# interfaces.net
KiCad netlist of a schematic drawn in Altium Designer
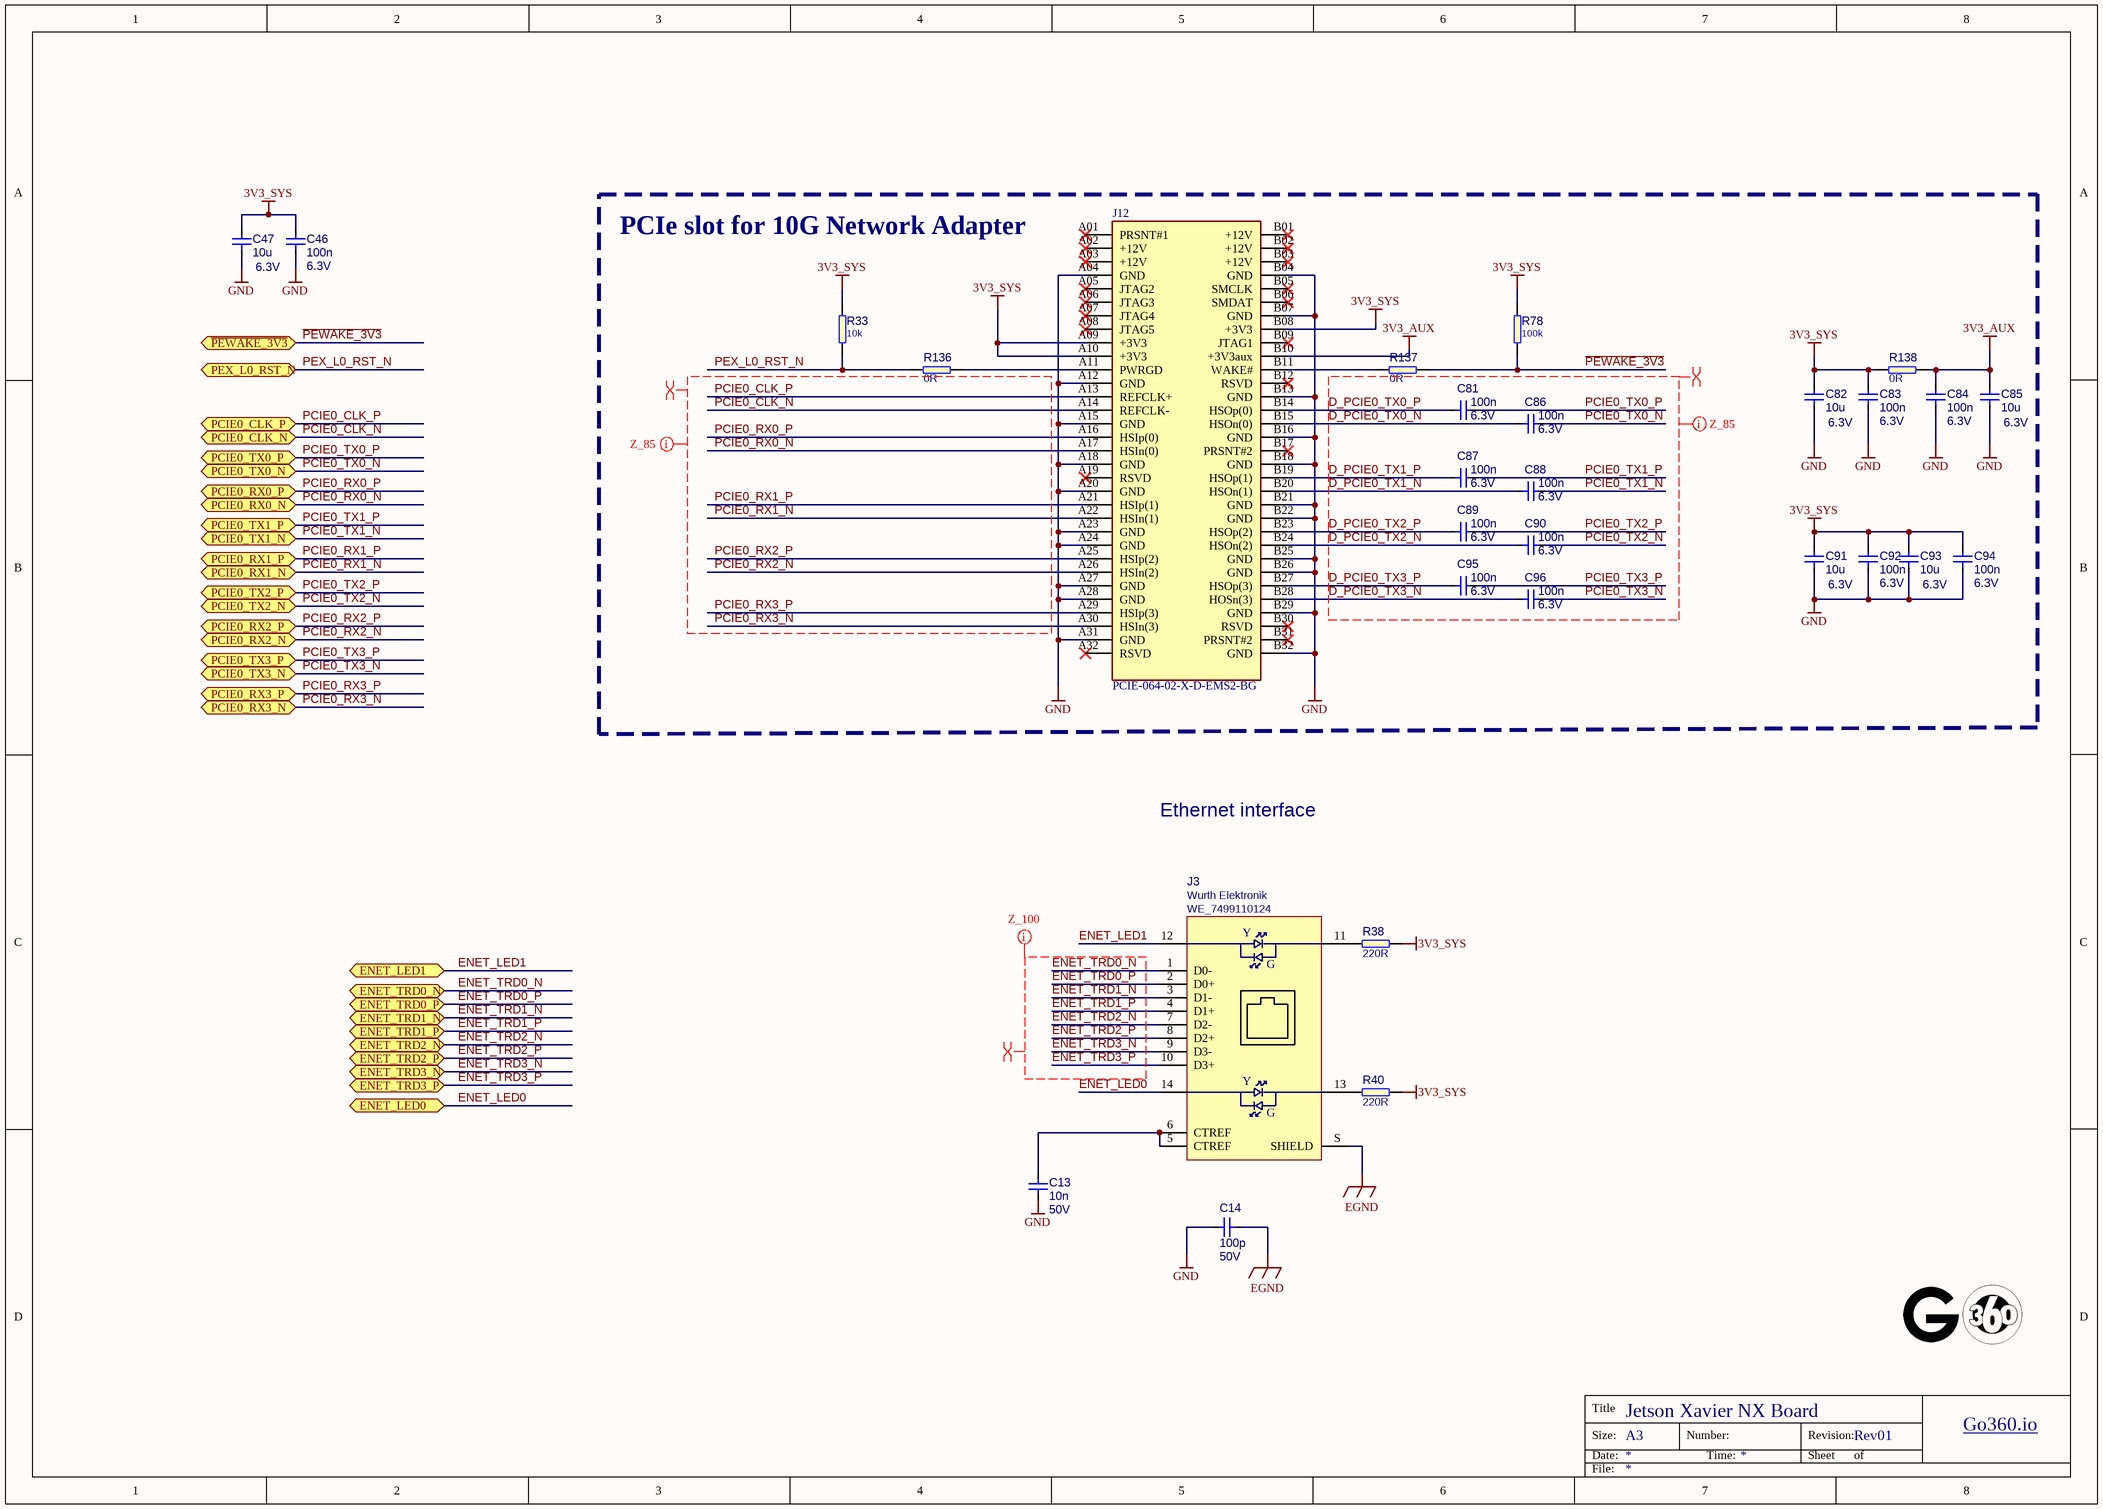
[diagram p0: interfaces.SchDoc]

(export (version "E")
  (design (tool "Eeschema 10.0.6"))
  (components
    (comp (ref "C13")
      (value "10n")
      (footprint "0402")
      (description "MLCC SMT Capacitor 10 nF 0402")
      (fields
        (field (name "PARTNUMBER") "C_10n_0402")
        (field (name "MANUFACTURER") "AVX")
        (field (name "VOLTAGE") "50V")
      )
      (libsource (lib "jetson-nano-baseboard") (part "C_10n_0402"))
    )
    (comp (ref "C14")
      (value "100p")
      (footprint "0805")
      (description "MLCC SMT Capacitor 100pF 0805")
      (fields
        (field (name "PARTNUMBER") "C_100p_0805")
        (field (name "MANUFACTURER") "AVX")
        (field (name "VOLTAGE") "50V")
      )
      (libsource (lib "jetson-nano-baseboard") (part "C_100p_0805"))
    )
    (comp (ref "C46")
      (value "100n")
      (footprint "0402")
      (description "MLCC SMT Capacitor 100n 0402")
      (fields
        (field (name "MANUFACTURER") "TDK")
        (field (name "PARTNUMBER") "C_100n_0402")
        (field (name "VOLTAGE") "6.3V")
      )
      (libsource (lib "jetson-nano-baseboard") (part "C_100n_0402"))
    )
    (comp (ref "C47")
      (value "10u")
      (footprint "0603")
      (description "MLCC SMT Capacitor 10uF 0603")
      (fields
        (field (name "MANUFACTURER") "Walsin")
        (field (name "PARTNUMBER") "C_10u_0603")
        (field (name "VOLTAGE") "6.3V")
      )
      (libsource (lib "jetson-nano-baseboard") (part "C_10u_0603"))
    )
    (comp (ref "C81")
      (value "100n")
      (footprint "0402")
      (description "MLCC SMT Capacitor 100n 0402")
      (fields
        (field (name "MANUFACTURER") "TDK")
        (field (name "PARTNUMBER") "C_100n_0402")
        (field (name "VOLTAGE") "6.3V")
      )
      (libsource (lib "jetson-nano-baseboard") (part "C_100n_0402"))
    )
    (comp (ref "C82")
      (value "10u")
      (footprint "0603")
      (description "MLCC SMT Capacitor 10uF 0603")
      (fields
        (field (name "MANUFACTURER") "Walsin")
        (field (name "PARTNUMBER") "C_10u_0603")
        (field (name "VOLTAGE") "6.3V")
      )
      (libsource (lib "jetson-nano-baseboard") (part "C_10u_0603"))
    )
    (comp (ref "C83")
      (value "100n")
      (footprint "0402")
      (description "MLCC SMT Capacitor 100n 0402")
      (fields
        (field (name "MANUFACTURER") "TDK")
        (field (name "PARTNUMBER") "C_100n_0402")
        (field (name "VOLTAGE") "6.3V")
      )
      (libsource (lib "jetson-nano-baseboard") (part "C_100n_0402"))
    )
    (comp (ref "C84")
      (value "100n")
      (footprint "0402")
      (description "MLCC SMT Capacitor 100n 0402")
      (fields
        (field (name "MANUFACTURER") "TDK")
        (field (name "PARTNUMBER") "C_100n_0402")
        (field (name "VOLTAGE") "6.3V")
      )
      (libsource (lib "jetson-nano-baseboard") (part "C_100n_0402"))
    )
    (comp (ref "C85")
      (value "10u")
      (footprint "0603")
      (description "MLCC SMT Capacitor 10uF 0603")
      (fields
        (field (name "MANUFACTURER") "Walsin")
        (field (name "PARTNUMBER") "C_10u_0603")
        (field (name "VOLTAGE") "6.3V")
      )
      (libsource (lib "jetson-nano-baseboard") (part "C_10u_0603"))
    )
    (comp (ref "C86")
      (value "100n")
      (footprint "0402")
      (description "MLCC SMT Capacitor 100n 0402")
      (fields
        (field (name "MANUFACTURER") "TDK")
        (field (name "PARTNUMBER") "C_100n_0402")
        (field (name "VOLTAGE") "6.3V")
      )
      (libsource (lib "jetson-nano-baseboard") (part "C_100n_0402"))
    )
    (comp (ref "C87")
      (value "100n")
      (footprint "0402")
      (description "MLCC SMT Capacitor 100n 0402")
      (fields
        (field (name "MANUFACTURER") "TDK")
        (field (name "PARTNUMBER") "C_100n_0402")
        (field (name "VOLTAGE") "6.3V")
      )
      (libsource (lib "jetson-nano-baseboard") (part "C_100n_0402"))
    )
    (comp (ref "C88")
      (value "100n")
      (footprint "0402")
      (description "MLCC SMT Capacitor 100n 0402")
      (fields
        (field (name "MANUFACTURER") "TDK")
        (field (name "PARTNUMBER") "C_100n_0402")
        (field (name "VOLTAGE") "6.3V")
      )
      (libsource (lib "jetson-nano-baseboard") (part "C_100n_0402"))
    )
    (comp (ref "C89")
      (value "100n")
      (footprint "0402")
      (description "MLCC SMT Capacitor 100n 0402")
      (fields
        (field (name "MANUFACTURER") "TDK")
        (field (name "PARTNUMBER") "C_100n_0402")
        (field (name "VOLTAGE") "6.3V")
      )
      (libsource (lib "jetson-nano-baseboard") (part "C_100n_0402"))
    )
    (comp (ref "C90")
      (value "100n")
      (footprint "0402")
      (description "MLCC SMT Capacitor 100n 0402")
      (fields
        (field (name "MANUFACTURER") "TDK")
        (field (name "PARTNUMBER") "C_100n_0402")
        (field (name "VOLTAGE") "6.3V")
      )
      (libsource (lib "jetson-nano-baseboard") (part "C_100n_0402"))
    )
    (comp (ref "C91")
      (value "10u")
      (footprint "0603")
      (description "MLCC SMT Capacitor 10uF 0603")
      (fields
        (field (name "MANUFACTURER") "Walsin")
        (field (name "PARTNUMBER") "C_10u_0603")
        (field (name "VOLTAGE") "6.3V")
      )
      (libsource (lib "jetson-nano-baseboard") (part "C_10u_0603"))
    )
    (comp (ref "C92")
      (value "100n")
      (footprint "0402")
      (description "MLCC SMT Capacitor 100n 0402")
      (fields
        (field (name "MANUFACTURER") "TDK")
        (field (name "PARTNUMBER") "C_100n_0402")
        (field (name "VOLTAGE") "6.3V")
      )
      (libsource (lib "jetson-nano-baseboard") (part "C_100n_0402"))
    )
    (comp (ref "C93")
      (value "10u")
      (footprint "0603")
      (description "MLCC SMT Capacitor 10uF 0603")
      (fields
        (field (name "MANUFACTURER") "Walsin")
        (field (name "PARTNUMBER") "C_10u_0603")
        (field (name "VOLTAGE") "6.3V")
      )
      (libsource (lib "jetson-nano-baseboard") (part "C_10u_0603"))
    )
    (comp (ref "C94")
      (value "100n")
      (footprint "0402")
      (description "MLCC SMT Capacitor 100n 0402")
      (fields
        (field (name "MANUFACTURER") "TDK")
        (field (name "PARTNUMBER") "C_100n_0402")
        (field (name "VOLTAGE") "6.3V")
      )
      (libsource (lib "jetson-nano-baseboard") (part "C_100n_0402"))
    )
    (comp (ref "C95")
      (value "100n")
      (footprint "0402")
      (description "MLCC SMT Capacitor 100n 0402")
      (fields
        (field (name "MANUFACTURER") "TDK")
        (field (name "PARTNUMBER") "C_100n_0402")
        (field (name "VOLTAGE") "6.3V")
      )
      (libsource (lib "jetson-nano-baseboard") (part "C_100n_0402"))
    )
    (comp (ref "C96")
      (value "100n")
      (footprint "0402")
      (description "MLCC SMT Capacitor 100n 0402")
      (fields
        (field (name "MANUFACTURER") "TDK")
        (field (name "PARTNUMBER") "C_100n_0402")
        (field (name "VOLTAGE") "6.3V")
      )
      (libsource (lib "jetson-nano-baseboard") (part "C_100n_0402"))
    )
    (comp (ref "J3")
      (value "WE_7499110124")
      (footprint "WE_7499110124")
      (description "LAN-Transformer WE-RJ45LAN 10/100/1000 BaseT")
      (fields (field (name "MANUFACTURER") "Wurth Elektronik") (field (name "PARTSYMBOL") "WE_7499110124"))
      (libsource (lib "jetson-nano-baseboard") (part "WE_7499111447"))
    )
    (comp (ref "J12")
      (value "PCIE-064-02-X-D-EMS2-BG")
      (footprint "SAMTEC_PCIE-064-02-X-D-EMS2-BG")
      (description "PCI EXPRESS EDGE MOUNT ASSEMBLY")
      (fields (field (name "MP") "PCIE-064-02-F-D-EMS2-BG") (field (name "MF") "Samtec"))
      (libsource (lib "jetson-nano-baseboard") (part "PCIE-064-02-X-D-EMS2-BG"))
    )
    (comp (ref "R33")
      (value "10k")
      (footprint "0402")
      (description "RES, 10k, 0402")
      (fields (field (name "PARTNUMBER") "R_10k_0402") (field (name "TOLERANCE") "1%"))
      (libsource (lib "jetson-nano-baseboard") (part "R_10k_0402"))
    )
    (comp (ref "R38")
      (value "220R")
      (footprint "0402")
      (description "RES, 220R, 0402")
      (fields (field (name "PARTNUMBER") "R_220R_0402") (field (name "MANUFACTURER") "TE CONECTIVITY"))
      (libsource (lib "") (part "R_220R_0402_1"))
    )
    (comp (ref "R40")
      (value "220R")
      (footprint "0402")
      (description "RES, 220R, 0402")
      (fields (field (name "PARTNUMBER") "R_220R_0402") (field (name "MANUFACTURER") "TE CONECTIVITY"))
      (libsource (lib "jetson-nano-baseboard") (part "R_220R_0402"))
    )
    (comp (ref "R78")
      (value "100k")
      (footprint "0402")
      (description "SMT Resistor 100k 0402")
      (fields (field (name "PARTNUMBER") "R_100k_0402") (field (name "TOLERANCE") "1%"))
      (libsource (lib "jetson-nano-baseboard") (part "R_100k_0402"))
    )
    (comp (ref "R136")
      (value "0R")
      (footprint "0402")
      (description "RES, 0R, 0402")
      (fields (field (name "MANUFACTURER") "Panasonic") (field (name "PARTNUMBER") "R_0R_0402"))
      (libsource (lib "jetson-nano-baseboard") (part "R_0R_0402"))
    )
    (comp (ref "R137")
      (value "0R")
      (footprint "0402")
      (description "RES, 0R, 0402")
      (fields (field (name "MANUFACTURER") "Panasonic") (field (name "PARTNUMBER") "R_0R_0402"))
      (libsource (lib "jetson-nano-baseboard") (part "R_0R_0402"))
    )
    (comp (ref "R138")
      (value "0R")
      (footprint "0402")
      (description "RES, 0R, 0402")
      (fields (field (name "MANUFACTURER") "Panasonic") (field (name "PARTNUMBER") "R_0R_0402"))
      (libsource (lib "jetson-nano-baseboard") (part "R_0R_0402"))
    )
  )
  (nets
    (net (code "1") (name "/D_PCIE0_TX0_N") (class "Default")
      (node (ref "C86") (pin "1") (pinfunction "1_1") (pintype "passive"))
      (node (ref "J12") (pin "B15") (pinfunction "HSOn(0)_B15") (pintype "passive"))
    )
    (net (code "2") (name "/D_PCIE0_TX0_P") (class "Default")
      (node (ref "C81") (pin "1") (pinfunction "1_1") (pintype "passive"))
      (node (ref "J12") (pin "B14") (pinfunction "HSOp(0)_B14") (pintype "passive"))
    )
    (net (code "3") (name "/D_PCIE0_TX1_N") (class "Default")
      (node (ref "C88") (pin "1") (pinfunction "1_1") (pintype "passive"))
      (node (ref "J12") (pin "B20") (pinfunction "HSOn(1)_B20") (pintype "passive"))
    )
    (net (code "4") (name "/D_PCIE0_TX1_P") (class "Default")
      (node (ref "C87") (pin "1") (pinfunction "1_1") (pintype "passive"))
      (node (ref "J12") (pin "B19") (pinfunction "HSOp(1)_B19") (pintype "passive"))
    )
    (net (code "5") (name "/D_PCIE0_TX2_N") (class "Default")
      (node (ref "C90") (pin "1") (pinfunction "1_1") (pintype "passive"))
      (node (ref "J12") (pin "B24") (pinfunction "HSOn(2)_B24") (pintype "passive"))
    )
    (net (code "6") (name "/D_PCIE0_TX2_P") (class "Default")
      (node (ref "C89") (pin "1") (pinfunction "1_1") (pintype "passive"))
      (node (ref "J12") (pin "B23") (pinfunction "HSOp(2)_B23") (pintype "passive"))
    )
    (net (code "7") (name "/D_PCIE0_TX3_N") (class "Default")
      (node (ref "C96") (pin "1") (pinfunction "1_1") (pintype "passive"))
      (node (ref "J12") (pin "B28") (pinfunction "HOSn(3)_B28") (pintype "passive"))
    )
    (net (code "8") (name "/D_PCIE0_TX3_P") (class "Default")
      (node (ref "C95") (pin "1") (pinfunction "1_1") (pintype "passive"))
      (node (ref "J12") (pin "B27") (pinfunction "HSOp(3)_B27") (pintype "passive"))
    )
    (net (code "9") (name "/ENET_LED0") (class "Default")
      (node (ref "J3") (pin "14") (pinfunction "14_14") (pintype "passive"))
    )
    (net (code "10") (name "/ENET_LED1") (class "Default")
      (node (ref "J3") (pin "12") (pinfunction "12_12") (pintype "passive"))
    )
    (net (code "11") (name "/ENET_TRD0_N") (class "Default")
      (node (ref "J3") (pin "1") (pinfunction "D0-_1") (pintype "passive"))
    )
    (net (code "12") (name "/ENET_TRD0_P") (class "Default")
      (node (ref "J3") (pin "2") (pinfunction "D0+_2") (pintype "passive"))
    )
    (net (code "13") (name "/ENET_TRD1_N") (class "Default")
      (node (ref "J3") (pin "3") (pinfunction "D1-_3") (pintype "passive"))
    )
    (net (code "14") (name "/ENET_TRD1_P") (class "Default")
      (node (ref "J3") (pin "4") (pinfunction "D1+_4") (pintype "passive"))
    )
    (net (code "15") (name "/ENET_TRD2_N") (class "Default")
      (node (ref "J3") (pin "7") (pinfunction "D2-_7") (pintype "passive"))
    )
    (net (code "16") (name "/ENET_TRD2_P") (class "Default")
      (node (ref "J3") (pin "8") (pinfunction "D2+_8") (pintype "passive"))
    )
    (net (code "17") (name "/ENET_TRD3_N") (class "Default")
      (node (ref "J3") (pin "9") (pinfunction "D3-_9") (pintype "passive"))
    )
    (net (code "18") (name "/ENET_TRD3_P") (class "Default")
      (node (ref "J3") (pin "10") (pinfunction "D3+_10") (pintype "passive"))
    )
    (net (code "19") (name "/PCIE0_CLK_N") (class "Default")
      (node (ref "J12") (pin "A14") (pinfunction "REFCLK-_A14") (pintype "passive"))
    )
    (net (code "20") (name "/PCIE0_CLK_P") (class "Default")
      (node (ref "J12") (pin "A13") (pinfunction "REFCLK+_A13") (pintype "passive"))
    )
    (net (code "21") (name "/PCIE0_RX0_N") (class "Default")
      (node (ref "J12") (pin "A17") (pinfunction "HSIn(0)_A17") (pintype "passive"))
    )
    (net (code "22") (name "/PCIE0_RX0_P") (class "Default")
      (node (ref "J12") (pin "A16") (pinfunction "HSIp(0)_A16") (pintype "passive"))
    )
    (net (code "23") (name "/PCIE0_RX1_N") (class "Default")
      (node (ref "J12") (pin "A22") (pinfunction "HSIn(1)_A22") (pintype "passive"))
    )
    (net (code "24") (name "/PCIE0_RX1_P") (class "Default")
      (node (ref "J12") (pin "A21") (pinfunction "HSIp(1)_A21") (pintype "passive"))
    )
    (net (code "25") (name "/PCIE0_RX2_N") (class "Default")
      (node (ref "J12") (pin "A26") (pinfunction "HSIn(2)_A26") (pintype "passive"))
    )
    (net (code "26") (name "/PCIE0_RX2_P") (class "Default")
      (node (ref "J12") (pin "A25") (pinfunction "HSIp(2)_A25") (pintype "passive"))
    )
    (net (code "27") (name "/PCIE0_RX3_N") (class "Default")
      (node (ref "J12") (pin "A30") (pinfunction "HSIn(3)_A30") (pintype "passive"))
    )
    (net (code "28") (name "/PCIE0_RX3_P") (class "Default")
      (node (ref "J12") (pin "A29") (pinfunction "HSIp(3)_A29") (pintype "passive"))
    )
    (net (code "29") (name "/PCIE0_TX0_N") (class "Default")
      (node (ref "C86") (pin "2") (pinfunction "2_2") (pintype "passive"))
    )
    (net (code "30") (name "/PCIE0_TX0_P") (class "Default")
      (node (ref "C81") (pin "2") (pinfunction "2_2") (pintype "passive"))
    )
    (net (code "31") (name "/PCIE0_TX1_N") (class "Default")
      (node (ref "C88") (pin "2") (pinfunction "2_2") (pintype "passive"))
    )
    (net (code "32") (name "/PCIE0_TX1_P") (class "Default")
      (node (ref "C87") (pin "2") (pinfunction "2_2") (pintype "passive"))
    )
    (net (code "33") (name "/PCIE0_TX2_N") (class "Default")
      (node (ref "C90") (pin "2") (pinfunction "2_2") (pintype "passive"))
    )
    (net (code "34") (name "/PCIE0_TX2_P") (class "Default")
      (node (ref "C89") (pin "2") (pinfunction "2_2") (pintype "passive"))
    )
    (net (code "35") (name "/PCIE0_TX3_N") (class "Default")
      (node (ref "C96") (pin "2") (pinfunction "2_2") (pintype "passive"))
    )
    (net (code "36") (name "/PCIE0_TX3_P") (class "Default")
      (node (ref "C95") (pin "2") (pinfunction "2_2") (pintype "passive"))
    )
    (net (code "37") (name "/PEWAKE_3V3") (class "Default")
      (node (ref "R137") (pin "1") (pintype "passive"))
      (node (ref "R78") (pin "1") (pintype "passive"))
    )
    (net (code "38") (name "/PEX_L0_RST_N") (class "Default")
      (node (ref "R136") (pin "2") (pintype "passive"))
      (node (ref "R33") (pin "2") (pintype "passive"))
    )
    (net (code "39") (name "3V3_AUX") (class "Default")
      (node (ref "C84") (pin "2") (pinfunction "2_2") (pintype "passive"))
      (node (ref "C85") (pin "2") (pinfunction "2_2") (pintype "passive"))
      (node (ref "J12") (pin "B10") (pinfunction "+3V3aux_B10") (pintype "passive"))
      (node (ref "R138") (pin "1") (pintype "passive"))
    )
    (net (code "40") (name "3V3_SYS") (class "Default")
      (node (ref "C46") (pin "2") (pinfunction "2_2") (pintype "passive"))
      (node (ref "C47") (pin "2") (pinfunction "2_2") (pintype "passive"))
      (node (ref "C82") (pin "2") (pinfunction "2_2") (pintype "passive"))
      (node (ref "C83") (pin "2") (pinfunction "2_2") (pintype "passive"))
      (node (ref "C91") (pin "2") (pinfunction "2_2") (pintype "passive"))
      (node (ref "C92") (pin "2") (pinfunction "2_2") (pintype "passive"))
      (node (ref "C93") (pin "2") (pinfunction "2_2") (pintype "passive"))
      (node (ref "C94") (pin "2") (pinfunction "2_2") (pintype "passive"))
      (node (ref "J12") (pin "A09") (pinfunction "+3V3_A09") (pintype "passive"))
      (node (ref "J12") (pin "A10") (pinfunction "+3V3_A10") (pintype "passive"))
      (node (ref "J12") (pin "B08") (pinfunction "+3V3_B08") (pintype "passive"))
      (node (ref "R138") (pin "2") (pintype "passive"))
      (node (ref "R33") (pin "1") (pintype "passive"))
      (node (ref "R38") (pin "2") (pintype "passive"))
      (node (ref "R40") (pin "1") (pintype "passive"))
      (node (ref "R78") (pin "2") (pintype "passive"))
    )
    (net (code "41") (name "EGND") (class "Default")
      (node (ref "C14") (pin "1") (pinfunction "1_1") (pintype "passive"))
      (node (ref "J3") (pin "S") (pinfunction "SHIELD_S") (pintype "passive"))
    )
    (net (code "42") (name "GND") (class "Default")
      (node (ref "C13") (pin "2") (pinfunction "2_2") (pintype "passive"))
      (node (ref "C14") (pin "2") (pinfunction "2_2") (pintype "passive"))
      (node (ref "C46") (pin "1") (pinfunction "1_1") (pintype "passive"))
      (node (ref "C47") (pin "1") (pinfunction "1_1") (pintype "passive"))
      (node (ref "C82") (pin "1") (pinfunction "1_1") (pintype "passive"))
      (node (ref "C83") (pin "1") (pinfunction "1_1") (pintype "passive"))
      (node (ref "C84") (pin "1") (pinfunction "1_1") (pintype "passive"))
      (node (ref "C85") (pin "1") (pinfunction "1_1") (pintype "passive"))
      (node (ref "C91") (pin "1") (pinfunction "1_1") (pintype "passive"))
      (node (ref "C92") (pin "1") (pinfunction "1_1") (pintype "passive"))
      (node (ref "C93") (pin "1") (pinfunction "1_1") (pintype "passive"))
      (node (ref "C94") (pin "1") (pinfunction "1_1") (pintype "passive"))
      (node (ref "J12") (pin "A04") (pinfunction "GND_A04") (pintype "passive"))
      (node (ref "J12") (pin "A12") (pinfunction "GND_A12") (pintype "passive"))
      (node (ref "J12") (pin "A15") (pinfunction "GND_A15") (pintype "passive"))
      (node (ref "J12") (pin "A18") (pinfunction "GND_A18") (pintype "passive"))
      (node (ref "J12") (pin "A20") (pinfunction "GND_A20") (pintype "passive"))
      (node (ref "J12") (pin "A23") (pinfunction "GND_A23") (pintype "passive"))
      (node (ref "J12") (pin "A24") (pinfunction "GND_A24") (pintype "passive"))
      (node (ref "J12") (pin "A27") (pinfunction "GND_A27") (pintype "passive"))
      (node (ref "J12") (pin "A28") (pinfunction "GND_A28") (pintype "passive"))
      (node (ref "J12") (pin "A31") (pinfunction "GND_A31") (pintype "passive"))
      (node (ref "J12") (pin "B04") (pinfunction "GND_B04") (pintype "passive"))
      (node (ref "J12") (pin "B07") (pinfunction "GND_B07") (pintype "passive"))
      (node (ref "J12") (pin "B13") (pinfunction "GND_B13") (pintype "passive"))
      (node (ref "J12") (pin "B16") (pinfunction "GND_B16") (pintype "passive"))
      (node (ref "J12") (pin "B18") (pinfunction "GND_B18") (pintype "passive"))
      (node (ref "J12") (pin "B21") (pinfunction "GND_B21") (pintype "passive"))
      (node (ref "J12") (pin "B22") (pinfunction "GND_B22") (pintype "passive"))
      (node (ref "J12") (pin "B25") (pinfunction "GND_B25") (pintype "passive"))
      (node (ref "J12") (pin "B26") (pinfunction "GND_B26") (pintype "passive"))
      (node (ref "J12") (pin "B29") (pinfunction "GND_B29") (pintype "passive"))
      (node (ref "J12") (pin "B32") (pinfunction "GND_B32") (pintype "passive"))
    )
    (net (code "43") (name "Net-(C13-Pad1)") (class "Default")
      (node (ref "C13") (pin "1") (pinfunction "1_1") (pintype "passive"))
      (node (ref "J3") (pin "5") (pinfunction "CTREF_5") (pintype "passive"))
      (node (ref "J3") (pin "6") (pinfunction "CTREF_6") (pintype "passive"))
    )
    (net (code "44") (name "Net-(J3-Pad11)") (class "Default")
      (node (ref "J3") (pin "11") (pinfunction "11_11") (pintype "passive"))
      (node (ref "R38") (pin "1") (pintype "passive"))
    )
    (net (code "45") (name "Net-(J3-Pad13)") (class "Default")
      (node (ref "J3") (pin "13") (pinfunction "13_13") (pintype "passive"))
      (node (ref "R40") (pin "2") (pintype "passive"))
    )
    (net (code "46") (name "Net-(J12-PWRGD)") (class "Default")
      (node (ref "J12") (pin "A11") (pinfunction "PWRGD_A11") (pintype "passive"))
      (node (ref "R136") (pin "1") (pintype "passive"))
    )
    (net (code "47") (name "Net-(J12-WAKE#)") (class "Default")
      (node (ref "J12") (pin "B11") (pinfunction "WAKE#_B11") (pintype "passive"))
      (node (ref "R137") (pin "2") (pintype "passive"))
    )
    (net (code "48") (name "unconnected-(J12-+12V-PadA02)") (class "Default")
      (node (ref "J12") (pin "A02") (pinfunction "+12V_A02") (pintype "passive+no_connect"))
    )
    (net (code "49") (name "unconnected-(J12-+12V-PadA03)") (class "Default")
      (node (ref "J12") (pin "A03") (pinfunction "+12V_A03") (pintype "passive+no_connect"))
    )
    (net (code "50") (name "unconnected-(J12-+12V-PadB01)") (class "Default")
      (node (ref "J12") (pin "B01") (pinfunction "+12V_B01") (pintype "passive+no_connect"))
    )
    (net (code "51") (name "unconnected-(J12-+12V-PadB02)") (class "Default")
      (node (ref "J12") (pin "B02") (pinfunction "+12V_B02") (pintype "passive+no_connect"))
    )
    (net (code "52") (name "unconnected-(J12-+12V-PadB03)") (class "Default")
      (node (ref "J12") (pin "B03") (pinfunction "+12V_B03") (pintype "passive+no_connect"))
    )
    (net (code "53") (name "unconnected-(J12-JTAG1-PadB09)") (class "Default")
      (node (ref "J12") (pin "B09") (pinfunction "JTAG1_B09") (pintype "passive+no_connect"))
    )
    (net (code "54") (name "unconnected-(J12-JTAG2-PadA05)") (class "Default")
      (node (ref "J12") (pin "A05") (pinfunction "JTAG2_A05") (pintype "passive+no_connect"))
    )
    (net (code "55") (name "unconnected-(J12-JTAG3-PadA06)") (class "Default")
      (node (ref "J12") (pin "A06") (pinfunction "JTAG3_A06") (pintype "passive+no_connect"))
    )
    (net (code "56") (name "unconnected-(J12-JTAG4-PadA07)") (class "Default")
      (node (ref "J12") (pin "A07") (pinfunction "JTAG4_A07") (pintype "passive+no_connect"))
    )
    (net (code "57") (name "unconnected-(J12-JTAG5-PadA08)") (class "Default")
      (node (ref "J12") (pin "A08") (pinfunction "JTAG5_A08") (pintype "passive+no_connect"))
    )
    (net (code "58") (name "unconnected-(J12-PRSNT#1-PadA01)") (class "Default")
      (node (ref "J12") (pin "A01") (pinfunction "PRSNT#1_A01") (pintype "passive+no_connect"))
    )
    (net (code "59") (name "unconnected-(J12-PRSNT#2-PadB17)") (class "Default")
      (node (ref "J12") (pin "B17") (pinfunction "PRSNT#2_B17") (pintype "passive+no_connect"))
    )
    (net (code "60") (name "unconnected-(J12-PRSNT#2-PadB31)") (class "Default")
      (node (ref "J12") (pin "B31") (pinfunction "PRSNT#2_B31") (pintype "passive+no_connect"))
    )
    (net (code "61") (name "unconnected-(J12-RSVD-PadA19)") (class "Default")
      (node (ref "J12") (pin "A19") (pinfunction "RSVD_A19") (pintype "passive+no_connect"))
    )
    (net (code "62") (name "unconnected-(J12-RSVD-PadA32)") (class "Default")
      (node (ref "J12") (pin "A32") (pinfunction "RSVD_A32") (pintype "passive+no_connect"))
    )
    (net (code "63") (name "unconnected-(J12-RSVD-PadB12)") (class "Default")
      (node (ref "J12") (pin "B12") (pinfunction "RSVD_B12") (pintype "passive+no_connect"))
    )
    (net (code "64") (name "unconnected-(J12-RSVD-PadB30)") (class "Default")
      (node (ref "J12") (pin "B30") (pinfunction "RSVD_B30") (pintype "passive+no_connect"))
    )
    (net (code "65") (name "unconnected-(J12-SMCLK-PadB05)") (class "Default")
      (node (ref "J12") (pin "B05") (pinfunction "SMCLK_B05") (pintype "passive+no_connect"))
    )
    (net (code "66") (name "unconnected-(J12-SMDAT-PadB06)") (class "Default")
      (node (ref "J12") (pin "B06") (pinfunction "SMDAT_B06") (pintype "passive+no_connect"))
    )
  )
)
